# Pullup_resistors.net
KiCad netlist of a schematic drawn in EAGLE
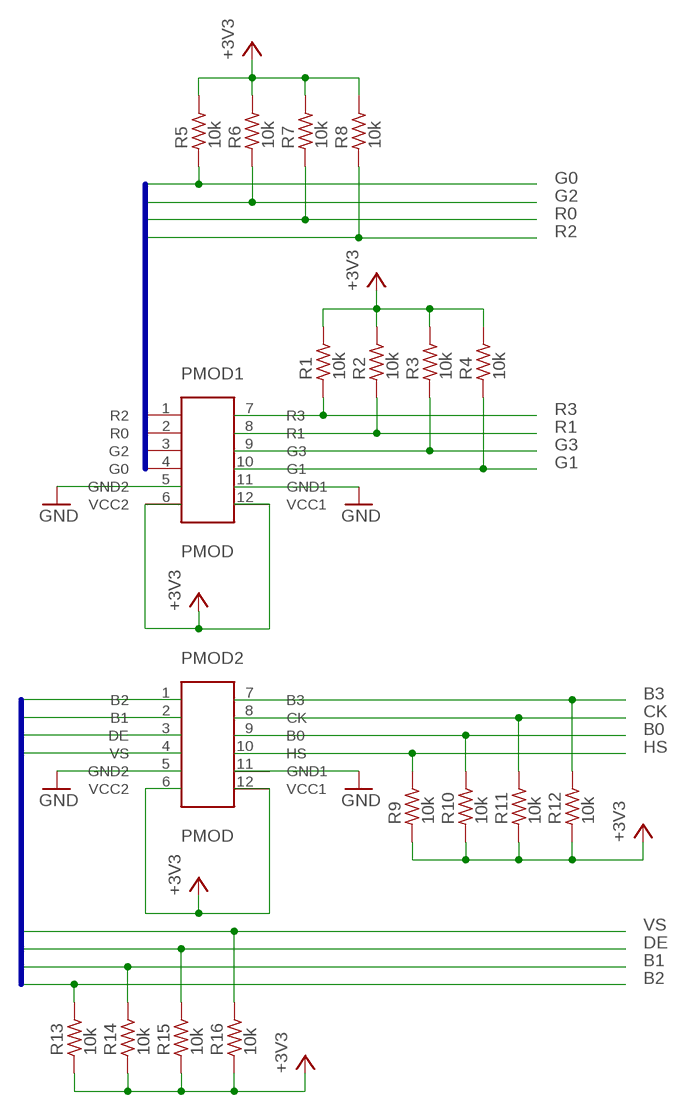
[diagram p0: schematic, sheet 1]

(export (version "E")
  (design (tool "Eeschema 10.0.6"))
  (components
    (comp (ref "PMOD1")
      (value "PMOD")
      (footprint "eagle-import:MA06-2")
      (libsource (lib "eagle-import") (part "PMOD"))
    )
    (comp (ref "PMOD2")
      (value "PMOD")
      (footprint "eagle-import:MA06-2")
      (libsource (lib "eagle-import") (part "PMOD 2_PMOD"))
    )
    (comp (ref "R1")
      (value "10k")
      (footprint "eagle-import:RC-MASTER-SMD_R0603MP")
      (libsource (lib "eagle-import") (part "RC-MASTER-SMD_R_0603MP"))
    )
    (comp (ref "R2")
      (value "10k")
      (footprint "eagle-import:RC-MASTER-SMD_R0603MP")
      (libsource (lib "eagle-import") (part "RC-MASTER-SMD_R_0603MP"))
    )
    (comp (ref "R3")
      (value "10k")
      (footprint "eagle-import:RC-MASTER-SMD_R0603MP")
      (libsource (lib "eagle-import") (part "RC-MASTER-SMD_R_0603MP"))
    )
    (comp (ref "R4")
      (value "10k")
      (footprint "eagle-import:RC-MASTER-SMD_R0603MP")
      (libsource (lib "eagle-import") (part "RC-MASTER-SMD_R_0603MP"))
    )
    (comp (ref "R5")
      (value "10k")
      (footprint "eagle-import:RC-MASTER-SMD_R0603MP")
      (libsource (lib "eagle-import") (part "RC-MASTER-SMD_R_0603MP"))
    )
    (comp (ref "R6")
      (value "10k")
      (footprint "eagle-import:RC-MASTER-SMD_R0603MP")
      (libsource (lib "eagle-import") (part "RC-MASTER-SMD_R_0603MP"))
    )
    (comp (ref "R7")
      (value "10k")
      (footprint "eagle-import:RC-MASTER-SMD_R0603MP")
      (libsource (lib "eagle-import") (part "RC-MASTER-SMD_R_0603MP"))
    )
    (comp (ref "R8")
      (value "10k")
      (footprint "eagle-import:RC-MASTER-SMD_R0603MP")
      (libsource (lib "eagle-import") (part "RC-MASTER-SMD_R_0603MP"))
    )
    (comp (ref "R9")
      (value "10k")
      (footprint "eagle-import:RC-MASTER-SMD_R0603MP")
      (libsource (lib "eagle-import") (part "RC-MASTER-SMD_R_0603MP"))
    )
    (comp (ref "R10")
      (value "10k")
      (footprint "eagle-import:RC-MASTER-SMD_R0603MP")
      (libsource (lib "eagle-import") (part "RC-MASTER-SMD_R_0603MP"))
    )
    (comp (ref "R11")
      (value "10k")
      (footprint "eagle-import:RC-MASTER-SMD_R0603MP")
      (libsource (lib "eagle-import") (part "RC-MASTER-SMD_R_0603MP"))
    )
    (comp (ref "R12")
      (value "10k")
      (footprint "eagle-import:RC-MASTER-SMD_R0603MP")
      (libsource (lib "eagle-import") (part "RC-MASTER-SMD_R_0603MP"))
    )
    (comp (ref "R13")
      (value "10k")
      (footprint "eagle-import:RC-MASTER-SMD_R0603MP")
      (libsource (lib "eagle-import") (part "RC-MASTER-SMD_R_0603MP"))
    )
    (comp (ref "R14")
      (value "10k")
      (footprint "eagle-import:RC-MASTER-SMD_R0603MP")
      (libsource (lib "eagle-import") (part "RC-MASTER-SMD_R_0603MP"))
    )
    (comp (ref "R15")
      (value "10k")
      (footprint "eagle-import:RC-MASTER-SMD_R0603MP")
      (libsource (lib "eagle-import") (part "RC-MASTER-SMD_R_0603MP"))
    )
    (comp (ref "R16")
      (value "10k")
      (footprint "eagle-import:RC-MASTER-SMD_R0603MP")
      (libsource (lib "eagle-import") (part "RC-MASTER-SMD_R_0603MP"))
    )
  )
  (nets
    (net (code "1") (name "+3V3") (class "Default")
      (node (ref "PMOD1") (pin "12") (pinfunction "VCC1_12") (pintype "bidirectional"))
      (node (ref "PMOD1") (pin "6") (pinfunction "VCC2_6") (pintype "bidirectional"))
      (node (ref "PMOD2") (pin "12") (pinfunction "VCC1_12") (pintype "bidirectional"))
      (node (ref "PMOD2") (pin "6") (pinfunction "VCC2_6") (pintype "bidirectional"))
      (node (ref "R1") (pin "2") (pinfunction "2_2") (pintype "passive"))
      (node (ref "R10") (pin "1") (pinfunction "1_1") (pintype "passive"))
      (node (ref "R11") (pin "1") (pinfunction "1_1") (pintype "passive"))
      (node (ref "R12") (pin "1") (pinfunction "1_1") (pintype "passive"))
      (node (ref "R13") (pin "1") (pinfunction "1_1") (pintype "passive"))
      (node (ref "R14") (pin "1") (pinfunction "1_1") (pintype "passive"))
      (node (ref "R15") (pin "1") (pinfunction "1_1") (pintype "passive"))
      (node (ref "R16") (pin "1") (pinfunction "1_1") (pintype "passive"))
      (node (ref "R2") (pin "2") (pinfunction "2_2") (pintype "passive"))
      (node (ref "R3") (pin "2") (pinfunction "2_2") (pintype "passive"))
      (node (ref "R4") (pin "2") (pinfunction "2_2") (pintype "passive"))
      (node (ref "R5") (pin "2") (pinfunction "2_2") (pintype "passive"))
      (node (ref "R6") (pin "2") (pinfunction "2_2") (pintype "passive"))
      (node (ref "R7") (pin "2") (pinfunction "2_2") (pintype "passive"))
      (node (ref "R8") (pin "2") (pinfunction "2_2") (pintype "passive"))
      (node (ref "R9") (pin "1") (pinfunction "1_1") (pintype "passive"))
    )
    (net (code "2") (name "/B0") (class "Default")
      (node (ref "PMOD2") (pin "9") (pinfunction "B0_9") (pintype "bidirectional"))
      (node (ref "R10") (pin "2") (pinfunction "2_2") (pintype "passive"))
    )
    (net (code "3") (name "/B1") (class "Default")
      (node (ref "R14") (pin "2") (pinfunction "2_2") (pintype "passive"))
    )
    (net (code "4") (name "/B2") (class "Default")
      (node (ref "R13") (pin "2") (pinfunction "2_2") (pintype "passive"))
    )
    (net (code "5") (name "/B3") (class "Default")
      (node (ref "PMOD2") (pin "7") (pinfunction "B3_7") (pintype "bidirectional"))
      (node (ref "R12") (pin "2") (pinfunction "2_2") (pintype "passive"))
    )
    (net (code "6") (name "/CK") (class "Default")
      (node (ref "PMOD2") (pin "8") (pinfunction "CK_8") (pintype "bidirectional"))
      (node (ref "R11") (pin "2") (pinfunction "2_2") (pintype "passive"))
    )
    (net (code "7") (name "/DE") (class "Default")
      (node (ref "R15") (pin "2") (pinfunction "2_2") (pintype "passive"))
    )
    (net (code "8") (name "/G0") (class "Default")
      (node (ref "R5") (pin "1") (pinfunction "1_1") (pintype "passive"))
    )
    (net (code "9") (name "/G1") (class "Default")
      (node (ref "PMOD1") (pin "10") (pinfunction "G1_10") (pintype "bidirectional"))
      (node (ref "R4") (pin "1") (pinfunction "1_1") (pintype "passive"))
    )
    (net (code "10") (name "/G2") (class "Default")
      (node (ref "R6") (pin "1") (pinfunction "1_1") (pintype "passive"))
    )
    (net (code "11") (name "/G3") (class "Default")
      (node (ref "PMOD1") (pin "9") (pinfunction "G3_9") (pintype "bidirectional"))
      (node (ref "R3") (pin "1") (pinfunction "1_1") (pintype "passive"))
    )
    (net (code "12") (name "/HS") (class "Default")
      (node (ref "PMOD2") (pin "10") (pinfunction "HS_10") (pintype "bidirectional"))
      (node (ref "R9") (pin "2") (pinfunction "2_2") (pintype "passive"))
    )
    (net (code "13") (name "/R0") (class "Default")
      (node (ref "R7") (pin "1") (pinfunction "1_1") (pintype "passive"))
    )
    (net (code "14") (name "/R1") (class "Default")
      (node (ref "PMOD1") (pin "8") (pinfunction "R1_8") (pintype "bidirectional"))
      (node (ref "R2") (pin "1") (pinfunction "1_1") (pintype "passive"))
    )
    (net (code "15") (name "/R2") (class "Default")
      (node (ref "R8") (pin "1") (pinfunction "1_1") (pintype "passive"))
    )
    (net (code "16") (name "/R3") (class "Default")
      (node (ref "PMOD1") (pin "7") (pinfunction "R3_7") (pintype "bidirectional"))
      (node (ref "R1") (pin "1") (pinfunction "1_1") (pintype "passive"))
    )
    (net (code "17") (name "/VS") (class "Default")
      (node (ref "R16") (pin "2") (pinfunction "2_2") (pintype "passive"))
    )
    (net (code "18") (name "GND") (class "Default")
      (node (ref "PMOD1") (pin "11") (pinfunction "GND1_11") (pintype "bidirectional"))
      (node (ref "PMOD1") (pin "5") (pinfunction "GND2_5") (pintype "bidirectional"))
      (node (ref "PMOD2") (pin "11") (pinfunction "GND1_11") (pintype "bidirectional"))
      (node (ref "PMOD2") (pin "5") (pinfunction "GND2_5") (pintype "bidirectional"))
    )
    (net (code "19") (name "unconnected-(PMOD1-G0-Pad4)") (class "Default")
      (node (ref "PMOD1") (pin "4") (pinfunction "G0_4") (pintype "bidirectional"))
    )
    (net (code "20") (name "unconnected-(PMOD1-G2-Pad3)") (class "Default")
      (node (ref "PMOD1") (pin "3") (pinfunction "G2_3") (pintype "bidirectional"))
    )
    (net (code "21") (name "unconnected-(PMOD1-R0-Pad2)") (class "Default")
      (node (ref "PMOD1") (pin "2") (pinfunction "R0_2") (pintype "bidirectional"))
    )
    (net (code "22") (name "unconnected-(PMOD1-R2-Pad1)") (class "Default")
      (node (ref "PMOD1") (pin "1") (pinfunction "R2_1") (pintype "bidirectional"))
    )
    (net (code "23") (name "unconnected-(PMOD2-B1-Pad2)") (class "Default")
      (node (ref "PMOD2") (pin "2") (pinfunction "B1_2") (pintype "bidirectional"))
    )
    (net (code "24") (name "unconnected-(PMOD2-B2-Pad1)") (class "Default")
      (node (ref "PMOD2") (pin "1") (pinfunction "B2_1") (pintype "bidirectional"))
    )
    (net (code "25") (name "unconnected-(PMOD2-DE-Pad3)") (class "Default")
      (node (ref "PMOD2") (pin "3") (pinfunction "DE_3") (pintype "bidirectional"))
    )
    (net (code "26") (name "unconnected-(PMOD2-VS-Pad4)") (class "Default")
      (node (ref "PMOD2") (pin "4") (pinfunction "VS_4") (pintype "bidirectional"))
    )
  )
)
